# 3.net
KiCad netlist of a schematic drawn in Altium Designer
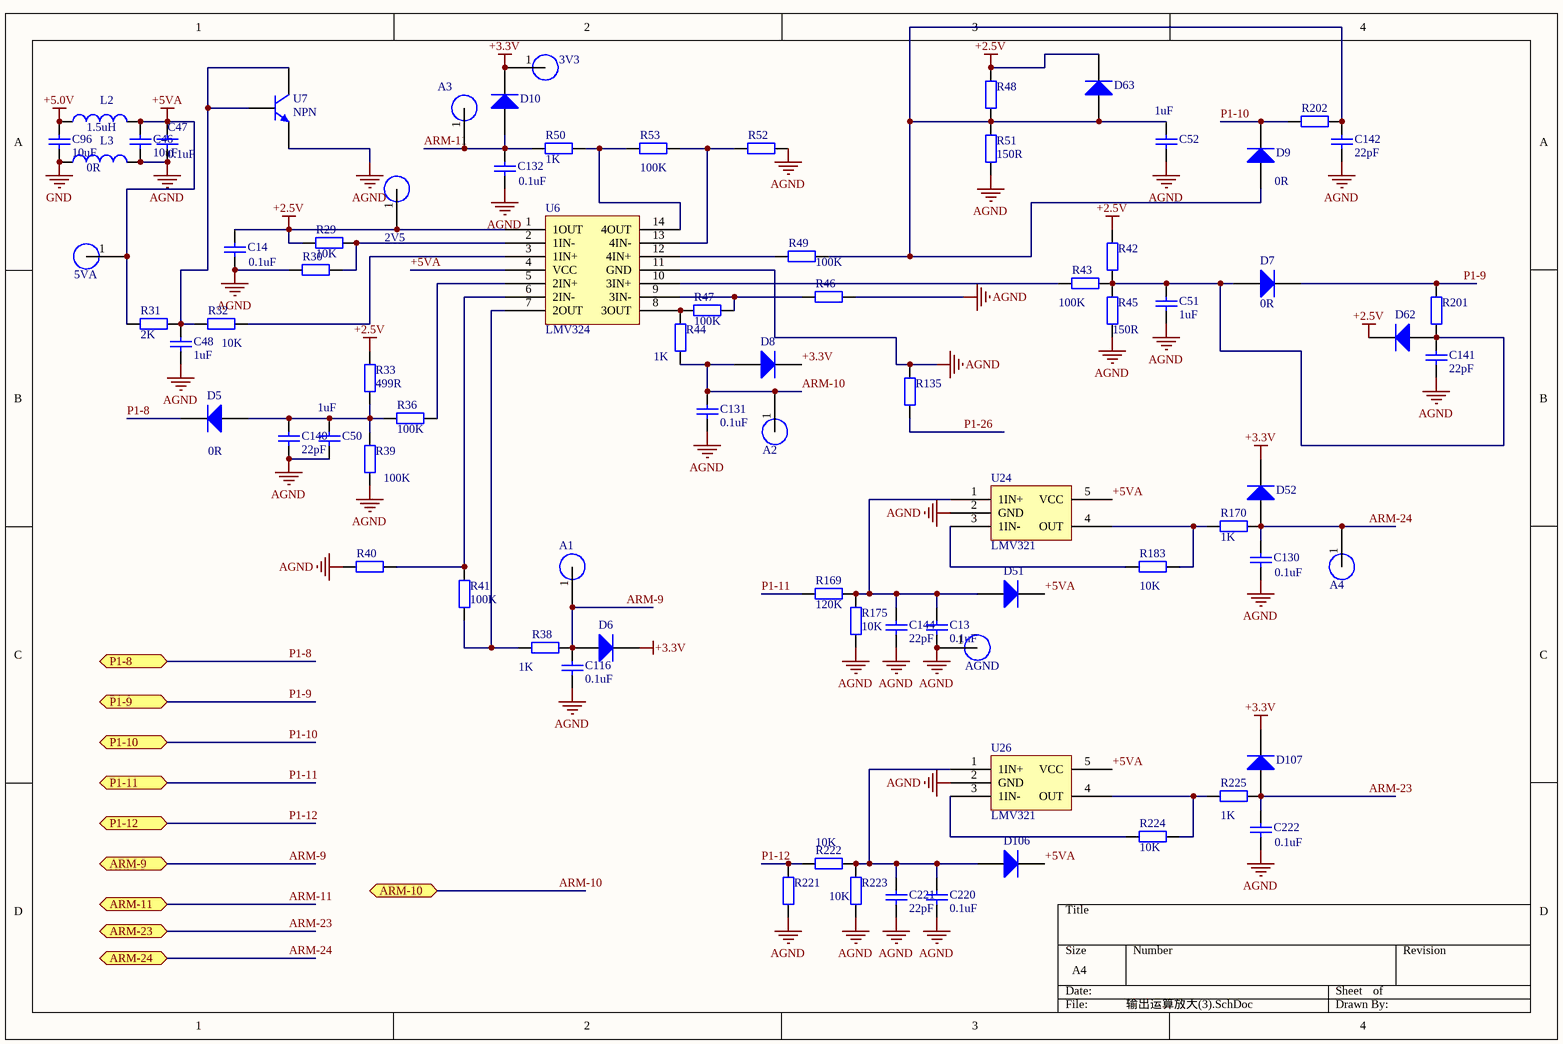
[diagram p0: 输出运算放大(3).SchDoc]

(export (version "E")
  (design (tool "Eeschema 10.0.6"))
  (components
    (comp (ref "2V5") (value "PIN") (footprint "圆形焊盘") (libsource (lib "圆孔") (part "Component_1")))
    (comp (ref "3V3") (value "PIN") (footprint "圆形焊盘") (libsource (lib "") (part "Component_1_1")))
    (comp (ref "5VA") (value "PIN") (footprint "圆形焊盘") (libsource (lib "") (part "Component_1_1")))
    (comp (ref "A1") (value "PIN") (footprint "圆形焊盘") (libsource (lib "圆孔") (part "Component_1")))
    (comp (ref "A2") (value "PIN") (footprint "圆形焊盘") (libsource (lib "圆孔") (part "Component_1")))
    (comp (ref "A3") (value "PIN") (footprint "圆形焊盘") (libsource (lib "圆孔") (part "Component_1")))
    (comp (ref "A4") (value "PIN") (footprint "圆形焊盘") (libsource (lib "圆孔") (part "Component_1")))
    (comp (ref "AGND") (value "PIN") (footprint "圆形焊盘") (libsource (lib "") (part "Component_1_1")))
    (comp (ref "C13")
      (value "0.1uF")
      (footprint "采集板3.0增加1路模拟量2:C0805")
      (description "Capacitor")
      (fields (field (name "Comment") "Cap") (field (name "PUBLISHER") "Altium Limited"))
      (libsource (lib "Miscellaneous Devices") (part "Cap"))
    )
    (comp (ref "C14")
      (value "0.1uF")
      (footprint "采集板3.0增加1路模拟量2:C0805")
      (description "Capacitor")
      (fields (field (name "Comment") "Cap") (field (name "PUBLISHER") "Altium Limited"))
      (libsource (lib "Miscellaneous Devices") (part "Cap"))
    )
    (comp (ref "C46")
      (value "10uF")
      (footprint "C1206")
      (description "Capacitor")
      (fields (field (name "Comment") "Cap") (field (name "PUBLISHER") "Altium Limited"))
      (libsource (lib "Miscellaneous Devices") (part "Cap"))
    )
    (comp (ref "C47")
      (value "0.1uF")
      (footprint "采集板3.0增加1路模拟量2:C0805")
      (description "Capacitor")
      (fields (field (name "Comment") "Cap") (field (name "PUBLISHER") "Altium Limited"))
      (libsource (lib "Miscellaneous Devices") (part "Cap"))
    )
    (comp (ref "C48")
      (value "1uF")
      (footprint "C0805")
      (description "Capacitor")
      (fields (field (name "Comment") "Cap") (field (name "PUBLISHER") "Altium Limited"))
      (libsource (lib "Miscellaneous Devices") (part "Cap"))
    )
    (comp (ref "C50")
      (value "1uF")
      (footprint "C0805")
      (description "Capacitor")
      (fields (field (name "Comment") "Cap") (field (name "PUBLISHER") "Altium Limited"))
      (libsource (lib "Miscellaneous Devices") (part "Cap"))
    )
    (comp (ref "C51")
      (value "1uF")
      (footprint "C0805")
      (description "Capacitor")
      (fields (field (name "Comment") "Cap") (field (name "PUBLISHER") "Altium Limited"))
      (libsource (lib "Miscellaneous Devices") (part "Cap"))
    )
    (comp (ref "C52")
      (value "1uF")
      (footprint "C0805")
      (description "Capacitor")
      (fields (field (name "Comment") "Cap") (field (name "PUBLISHER") "Altium Limited"))
      (libsource (lib "Miscellaneous Devices") (part "Cap"))
    )
    (comp (ref "C96")
      (value "10uF")
      (footprint "C1206")
      (description "Capacitor")
      (fields (field (name "Comment") "Cap") (field (name "PUBLISHER") "Altium Limited"))
      (libsource (lib "Miscellaneous Devices") (part "Cap"))
    )
    (comp (ref "C116")
      (value "0.1uF")
      (footprint "采集板3.0增加1路模拟量2:C0805")
      (description "Capacitor")
      (fields (field (name "Comment") "Cap") (field (name "PUBLISHER") "Altium Limited"))
      (libsource (lib "Miscellaneous Devices") (part "Cap"))
    )
    (comp (ref "C130")
      (value "0.1uF")
      (footprint "采集板3.0增加1路模拟量2:C0805")
      (description "Capacitor")
      (fields (field (name "Comment") "Cap") (field (name "PUBLISHER") "Altium Limited"))
      (libsource (lib "Miscellaneous Devices") (part "Cap"))
    )
    (comp (ref "C131")
      (value "0.1uF")
      (footprint "采集板3.0增加1路模拟量2:C0805")
      (description "Capacitor")
      (fields (field (name "Comment") "Cap") (field (name "PUBLISHER") "Altium Limited"))
      (libsource (lib "Miscellaneous Devices") (part "Cap"))
    )
    (comp (ref "C132")
      (value "0.1uF")
      (footprint "采集板3.0增加1路模拟量2:C0805")
      (description "Capacitor")
      (fields (field (name "Comment") "Cap") (field (name "PUBLISHER") "Altium Limited"))
      (libsource (lib "Miscellaneous Devices") (part "Cap"))
    )
    (comp (ref "C140")
      (value "22pF")
      (footprint "采集板3.0增加1路模拟量2:C0805")
      (description "Capacitor")
      (fields (field (name "Comment") "Cap") (field (name "PUBLISHER") "Altium Limited"))
      (libsource (lib "Miscellaneous Devices") (part "Cap"))
    )
    (comp (ref "C141")
      (value "22pF")
      (footprint "采集板3.0增加1路模拟量2:C0805")
      (description "Capacitor")
      (fields (field (name "Comment") "Cap") (field (name "PUBLISHER") "Altium Limited"))
      (libsource (lib "Miscellaneous Devices") (part "Cap"))
    )
    (comp (ref "C142")
      (value "22pF")
      (footprint "采集板3.0增加1路模拟量2:C0805")
      (description "Capacitor")
      (fields (field (name "Comment") "Cap") (field (name "PUBLISHER") "Altium Limited"))
      (libsource (lib "Miscellaneous Devices") (part "Cap"))
    )
    (comp (ref "C144")
      (value "22pF")
      (footprint "采集板3.0增加1路模拟量2:C0805")
      (description "Capacitor")
      (fields (field (name "Comment") "Cap") (field (name "PUBLISHER") "Altium Limited"))
      (libsource (lib "Miscellaneous Devices") (part "Cap"))
    )
    (comp (ref "C220")
      (value "0.1uF")
      (footprint "采集板3.0增加1路模拟量2:C0805")
      (description "Capacitor")
      (fields (field (name "Comment") "Cap") (field (name "PUBLISHER") "Altium Limited"))
      (libsource (lib "Miscellaneous Devices") (part "Cap"))
    )
    (comp (ref "C221")
      (value "22pF")
      (footprint "采集板3.0增加1路模拟量2:C0805")
      (description "Capacitor")
      (fields (field (name "Comment") "Cap") (field (name "PUBLISHER") "Altium Limited"))
      (libsource (lib "Miscellaneous Devices") (part "Cap"))
    )
    (comp (ref "C222")
      (value "0.1uF")
      (footprint "采集板3.0增加1路模拟量2:C0805")
      (description "Capacitor")
      (fields (field (name "Comment") "Cap") (field (name "PUBLISHER") "Altium Limited"))
      (libsource (lib "") (part "Cap_1"))
    )
    (comp (ref "D5")
      (value "0R")
      (footprint "SOD123")
      (description "1 Amp General Purpose Rectifier")
      (fields (field (name "Comment") "Diode 1N4007") (field (name "PUBLISHER") "Altium Limited"))
      (libsource (lib "Miscellaneous Devices") (part "Diode 1N4007"))
    )
    (comp (ref "D6")
      (value "Diode 1N4007")
      (footprint "SOD123")
      (description "1 Amp General Purpose Rectifier")
      (fields (field (name "PUBLISHER") "Altium Limited"))
      (libsource (lib "Miscellaneous Devices") (part "Diode 1N4007"))
    )
    (comp (ref "D7")
      (value "0R")
      (footprint "SOD123")
      (description "1 Amp General Purpose Rectifier")
      (fields (field (name "Comment") "Diode 1N4007") (field (name "PUBLISHER") "Altium Limited"))
      (libsource (lib "Miscellaneous Devices") (part "Diode 1N4007"))
    )
    (comp (ref "D8")
      (value "Diode 1N4007")
      (footprint "SOD123")
      (description "1 Amp General Purpose Rectifier")
      (fields (field (name "PUBLISHER") "Altium Limited"))
      (libsource (lib "Miscellaneous Devices") (part "Diode 1N4007"))
    )
    (comp (ref "D9")
      (value "0R")
      (footprint "SOD123")
      (description "1 Amp General Purpose Rectifier")
      (fields (field (name "Comment") "Diode 1N4007") (field (name "PUBLISHER") "Altium Limited"))
      (libsource (lib "Miscellaneous Devices") (part "Diode 1N4007"))
    )
    (comp (ref "D10")
      (value "Diode 1N4007")
      (footprint "SOD123")
      (description "1 Amp General Purpose Rectifier")
      (fields (field (name "PUBLISHER") "Altium Limited"))
      (libsource (lib "Miscellaneous Devices") (part "Diode 1N4007"))
    )
    (comp (ref "D51")
      (value "Diode 1N4007")
      (footprint "SOD123")
      (description "1 Amp General Purpose Rectifier")
      (fields (field (name "PUBLISHER") "Altium Limited"))
      (libsource (lib "Miscellaneous Devices") (part "Diode 1N4007"))
    )
    (comp (ref "D52")
      (value "Diode 1N4007")
      (footprint "SOD123")
      (description "1 Amp General Purpose Rectifier")
      (fields (field (name "PUBLISHER") "Altium Limited"))
      (libsource (lib "Miscellaneous Devices") (part "Diode 1N4007"))
    )
    (comp (ref "D62")
      (value "Diode 1N4007")
      (footprint "SOD123")
      (description "1 Amp General Purpose Rectifier")
      (fields (field (name "PUBLISHER") "Altium Limited"))
      (libsource (lib "Miscellaneous Devices") (part "Diode 1N4007"))
    )
    (comp (ref "D63")
      (value "Diode 1N4007")
      (footprint "SOD123")
      (description "1 Amp General Purpose Rectifier")
      (fields (field (name "PUBLISHER") "Altium Limited"))
      (libsource (lib "Miscellaneous Devices") (part "Diode 1N4007"))
    )
    (comp (ref "D106")
      (value "Diode 1N4007")
      (footprint "SOD123")
      (description "1 Amp General Purpose Rectifier")
      (fields (field (name "PUBLISHER") "Altium Limited"))
      (libsource (lib "Miscellaneous Devices") (part "Diode 1N4007"))
    )
    (comp (ref "D107")
      (value "Diode 1N4007")
      (footprint "SOD123")
      (description "1 Amp General Purpose Rectifier")
      (fields (field (name "PUBLISHER") "Altium Limited"))
      (libsource (lib "Miscellaneous Devices") (part "Diode 1N4007"))
    )
    (comp (ref "L2")
      (value "1.5uH")
      (footprint "C1206")
      (description "Inductor")
      (fields (field (name "PUBLISHER") "Altium Limited"))
      (libsource (lib "Miscellaneous Devices") (part "Inductor"))
    )
    (comp (ref "L3")
      (value "0R")
      (footprint "R1206")
      (description "Inductor")
      (fields (field (name "PUBLISHER") "Altium Limited"))
      (libsource (lib "Miscellaneous Devices") (part "Inductor"))
    )
    (comp (ref "R29")
      (value "10K")
      (footprint "采集板3.0增加1路模拟量2:R0805")
      (description "Resistor")
      (fields (field (name "Comment") "Res2") (field (name "PUBLISHER") "Altium Limited"))
      (libsource (lib "Miscellaneous Devices") (part "Res2"))
    )
    (comp (ref "R30")
      (value "Res2")
      (footprint "R0805")
      (description "Resistor")
      (fields (field (name "PUBLISHER") "Altium Limited"))
      (libsource (lib "") (part "Res2_3"))
    )
    (comp (ref "R31")
      (value "2K")
      (footprint "采集板3.0增加1路模拟量2:R0805")
      (description "Resistor")
      (fields (field (name "Comment") "Res2") (field (name "PUBLISHER") "Altium Limited"))
      (libsource (lib "") (part "Res2_3"))
    )
    (comp (ref "R32")
      (value "10K")
      (footprint "采集板3.0增加1路模拟量2:R0805")
      (description "Resistor")
      (fields (field (name "Comment") "Res2") (field (name "PUBLISHER") "Altium Limited"))
      (libsource (lib "Miscellaneous Devices") (part "Res2"))
    )
    (comp (ref "R33")
      (value "499R")
      (footprint "采集板3.0增加1路模拟量2:R0805")
      (description "Resistor")
      (fields (field (name "Comment") "Res2") (field (name "PUBLISHER") "Altium Limited"))
      (libsource (lib "") (part "Res2_1"))
    )
    (comp (ref "R36")
      (value "100K")
      (footprint "采集板3.0增加1路模拟量2:R0805")
      (description "Resistor")
      (fields (field (name "Comment") "Res2") (field (name "PUBLISHER") "Altium Limited"))
      (libsource (lib "") (part "Res2_3"))
    )
    (comp (ref "R38")
      (value "1K")
      (footprint "采集板3.0增加1路模拟量2:R0805")
      (description "Resistor")
      (fields (field (name "Comment") "Res2") (field (name "PUBLISHER") "Altium Limited"))
      (libsource (lib "") (part "Res2_3"))
    )
    (comp (ref "R39")
      (value "100K")
      (footprint "采集板3.0增加1路模拟量2:R0805")
      (description "Resistor")
      (fields (field (name "Comment") "Res2") (field (name "PUBLISHER") "Altium Limited"))
      (libsource (lib "") (part "Res2_2"))
    )
    (comp (ref "R40")
      (value "Res2")
      (footprint "R0805")
      (description "Resistor")
      (fields (field (name "PUBLISHER") "Altium Limited"))
      (libsource (lib "") (part "Res2_3"))
    )
    (comp (ref "R41")
      (value "100K")
      (footprint "采集板3.0增加1路模拟量2:R0805")
      (description "Resistor")
      (fields (field (name "Comment") "Res2") (field (name "PUBLISHER") "Altium Limited"))
      (libsource (lib "") (part "Res2_1"))
    )
    (comp (ref "R42")
      (value "Res2")
      (footprint "R0805")
      (description "Resistor")
      (fields (field (name "PUBLISHER") "Altium Limited"))
      (libsource (lib "") (part "Res2_1"))
    )
    (comp (ref "R43")
      (value "100K")
      (footprint "采集板3.0增加1路模拟量2:R0805")
      (description "Resistor")
      (fields (field (name "Comment") "Res2") (field (name "PUBLISHER") "Altium Limited"))
      (libsource (lib "Miscellaneous Devices") (part "Res2"))
    )
    (comp (ref "R44")
      (value "1K")
      (footprint "采集板3.0增加1路模拟量2:R0805")
      (description "Resistor")
      (fields (field (name "Comment") "Res2") (field (name "PUBLISHER") "Altium Limited"))
      (libsource (lib "") (part "Res2_2"))
    )
    (comp (ref "R45")
      (value "150R")
      (footprint "R0805")
      (description "Resistor")
      (fields (field (name "Comment") "150") (field (name "PUBLISHER") "Altium Limited"))
      (libsource (lib "") (part "Res2_2"))
    )
    (comp (ref "R46")
      (value "Res2")
      (footprint "R0805")
      (description "Resistor")
      (fields (field (name "PUBLISHER") "Altium Limited"))
      (libsource (lib "Miscellaneous Devices") (part "Res2"))
    )
    (comp (ref "R47")
      (value "100K")
      (footprint "采集板3.0增加1路模拟量2:R0805")
      (description "Resistor")
      (fields (field (name "Comment") "Res2") (field (name "PUBLISHER") "Altium Limited"))
      (libsource (lib "") (part "Res2_3"))
    )
    (comp (ref "R48")
      (value "Res2")
      (footprint "R0805")
      (description "Resistor")
      (fields (field (name "PUBLISHER") "Altium Limited"))
      (libsource (lib "") (part "Res2_1"))
    )
    (comp (ref "R49")
      (value "100K")
      (footprint "采集板3.0增加1路模拟量2:R0805")
      (description "Resistor")
      (fields (field (name "Comment") "Res2") (field (name "PUBLISHER") "Altium Limited"))
      (libsource (lib "Miscellaneous Devices") (part "Res2"))
    )
    (comp (ref "R50")
      (value "1K")
      (footprint "采集板3.0增加1路模拟量2:R0805")
      (description "Resistor")
      (fields (field (name "Comment") "Res2") (field (name "PUBLISHER") "Altium Limited"))
      (libsource (lib "") (part "Res2_3"))
    )
    (comp (ref "R51")
      (value "150R")
      (footprint "R0805")
      (description "Resistor")
      (fields (field (name "Comment") "Res2") (field (name "PUBLISHER") "Altium Limited"))
      (libsource (lib "") (part "Res2_2"))
    )
    (comp (ref "R52")
      (value "Res2")
      (footprint "R0805")
      (description "Resistor")
      (fields (field (name "PUBLISHER") "Altium Limited"))
      (libsource (lib "") (part "Res2_3"))
    )
    (comp (ref "R53")
      (value "100K")
      (footprint "采集板3.0增加1路模拟量2:R0805")
      (description "Resistor")
      (fields (field (name "Comment") "Res2") (field (name "PUBLISHER") "Altium Limited"))
      (libsource (lib "Miscellaneous Devices") (part "Res2"))
    )
    (comp (ref "R135")
      (value "Res2")
      (footprint "采集板3.0增加1路模拟量2:R0805")
      (description "Resistor")
      (fields (field (name "PUBLISHER") "Altium Limited"))
      (libsource (lib "") (part "Res2_2"))
    )
    (comp (ref "R169")
      (value "120K")
      (footprint "采集板3.0增加1路模拟量2:R0805")
      (description "Resistor")
      (fields (field (name "Comment") "Res2") (field (name "PUBLISHER") "Altium Limited"))
      (libsource (lib "") (part "Res2_3"))
    )
    (comp (ref "R170")
      (value "1K")
      (footprint "采集板3.0增加1路模拟量2:R0805")
      (description "Resistor")
      (fields (field (name "Comment") "Res2") (field (name "PUBLISHER") "Altium Limited"))
      (libsource (lib "") (part "Res2_3"))
    )
    (comp (ref "R175")
      (value "10K")
      (footprint "采集板3.0增加1路模拟量2:R0805")
      (description "Resistor")
      (fields (field (name "Comment") "Res2") (field (name "PUBLISHER") "Altium Limited"))
      (libsource (lib "") (part "Res2_1"))
    )
    (comp (ref "R183")
      (value "10K")
      (footprint "采集板3.0增加1路模拟量2:R0805")
      (description "Resistor")
      (fields (field (name "Comment") "Res2") (field (name "PUBLISHER") "Altium Limited"))
      (libsource (lib "Miscellaneous Devices") (part "Res2"))
    )
    (comp (ref "R201")
      (value "Res2")
      (footprint "R0805")
      (description "Resistor")
      (fields (field (name "PUBLISHER") "Altium Limited"))
      (libsource (lib "") (part "Res2_1"))
    )
    (comp (ref "R202")
      (value "Res2")
      (footprint "R0805")
      (description "Resistor")
      (fields (field (name "PUBLISHER") "Altium Limited"))
      (libsource (lib "Miscellaneous Devices") (part "Res2"))
    )
    (comp (ref "R221")
      (value "Res2")
      (footprint "R0805")
      (description "Resistor")
      (fields (field (name "PUBLISHER") "Altium Limited"))
      (libsource (lib "") (part "Res2_2"))
    )
    (comp (ref "R222")
      (value "10K")
      (footprint "采集板3.0增加1路模拟量2:R0805")
      (description "Resistor")
      (fields (field (name "Comment") "Res2") (field (name "PUBLISHER") "Altium Limited"))
      (libsource (lib "Miscellaneous Devices") (part "Res2"))
    )
    (comp (ref "R223")
      (value "10K")
      (footprint "采集板3.0增加1路模拟量2:R0805")
      (description "Resistor")
      (fields (field (name "Comment") "Res2") (field (name "PUBLISHER") "Altium Limited"))
      (libsource (lib "") (part "Res2_2"))
    )
    (comp (ref "R224")
      (value "10K")
      (footprint "采集板3.0增加1路模拟量2:R0805")
      (description "Resistor")
      (fields (field (name "Comment") "Res2") (field (name "PUBLISHER") "Altium Limited"))
      (libsource (lib "") (part "Res2_3"))
    )
    (comp (ref "R225")
      (value "1K")
      (footprint "采集板3.0增加1路模拟量2:R0805")
      (description "Resistor")
      (fields (field (name "Comment") "Res2") (field (name "PUBLISHER") "Altium Limited"))
      (libsource (lib "") (part "Res2_4"))
    )
    (comp (ref "U6") (value "LMV324") (footprint "SOP-14") (libsource (lib "LMV324") (part "Component_1")))
    (comp (ref "U7")
      (value "NPN")
      (footprint "SOT23-3")
      (description "NPN Bipolar Transistor")
      (fields (field (name "PUBLISHER") "Altium Limited"))
      (libsource (lib "Miscellaneous Devices") (part "NPN"))
    )
    (comp (ref "U24") (value "LMV321") (footprint "SOT23-5") (libsource (lib "LMV321") (part "Component_1")))
    (comp (ref "U26") (value "LMV321") (footprint "SOT23-5") (libsource (lib "LMV321") (part "Component_1")))
  )
  (nets
    (net (code "1") (name "+2.5V") (class "Default")
      (node (ref "2V5") (pin "1") (pinfunction "1_1") (pintype "passive"))
      (node (ref "C14") (pin "2") (pinfunction "2_2") (pintype "passive"))
      (node (ref "D62") (pin "2") (pinfunction "K_2") (pintype "passive"))
      (node (ref "D63") (pin "2") (pinfunction "K_2") (pintype "passive"))
      (node (ref "R29") (pin "2") (pinfunction "2_2") (pintype "passive"))
      (node (ref "R33") (pin "2") (pinfunction "2_2") (pintype "passive"))
      (node (ref "R42") (pin "2") (pinfunction "2_2") (pintype "passive"))
      (node (ref "R48") (pin "2") (pinfunction "2_2") (pintype "passive"))
      (node (ref "U6") (pin "1") (pinfunction "1OUT_1") (pintype "passive"))
    )
    (net (code "2") (name "+3.3V") (class "Default")
      (node (ref "3V3") (pin "1") (pinfunction "1_1") (pintype "passive"))
      (node (ref "D10") (pin "2") (pinfunction "K_2") (pintype "passive"))
      (node (ref "D107") (pin "2") (pinfunction "K_2") (pintype "passive"))
      (node (ref "D52") (pin "2") (pinfunction "K_2") (pintype "passive"))
      (node (ref "D6") (pin "2") (pinfunction "K_2") (pintype "passive"))
      (node (ref "D8") (pin "2") (pinfunction "K_2") (pintype "passive"))
    )
    (net (code "3") (name "+5.0V") (class "Default")
      (node (ref "C96") (pin "1") (pinfunction "1_1") (pintype "passive"))
      (node (ref "L2") (pin "1") (pinfunction "1_1") (pintype "passive"))
    )
    (net (code "4") (name "+5VA") (class "Default")
      (node (ref "5VA") (pin "1") (pinfunction "1_1") (pintype "passive"))
      (node (ref "C46") (pin "1") (pinfunction "1_1") (pintype "passive"))
      (node (ref "C47") (pin "2") (pinfunction "2_2") (pintype "passive"))
      (node (ref "D106") (pin "2") (pinfunction "K_2") (pintype "passive"))
      (node (ref "D51") (pin "2") (pinfunction "K_2") (pintype "passive"))
      (node (ref "L2") (pin "2") (pinfunction "2_2") (pintype "passive"))
      (node (ref "R31") (pin "1") (pinfunction "1_1") (pintype "passive"))
      (node (ref "U24") (pin "5") (pinfunction "VCC_5") (pintype "passive"))
      (node (ref "U26") (pin "5") (pinfunction "VCC_5") (pintype "passive"))
      (node (ref "U6") (pin "4") (pinfunction "VCC_4") (pintype "passive"))
    )
    (net (code "5") (name "/ARM-9") (class "Default")
      (node (ref "A1") (pin "1") (pinfunction "1_1") (pintype "passive"))
      (node (ref "C116") (pin "1") (pinfunction "1_1") (pintype "passive"))
      (node (ref "D6") (pin "1") (pinfunction "A_1") (pintype "passive"))
      (node (ref "R38") (pin "2") (pinfunction "2_2") (pintype "passive"))
    )
    (net (code "6") (name "/ARM-10") (class "Default")
      (node (ref "A2") (pin "1") (pinfunction "1_1") (pintype "passive"))
      (node (ref "C131") (pin "1") (pinfunction "1_1") (pintype "passive"))
      (node (ref "D8") (pin "1") (pinfunction "A_1") (pintype "passive"))
      (node (ref "R44") (pin "2") (pinfunction "2_2") (pintype "passive"))
    )
    (net (code "7") (name "/ARM-11") (class "Default")
      (node (ref "A3") (pin "1") (pinfunction "1_1") (pintype "passive"))
      (node (ref "C132") (pin "2") (pinfunction "2_2") (pintype "passive"))
      (node (ref "D10") (pin "1") (pinfunction "A_1") (pintype "passive"))
      (node (ref "R50") (pin "1") (pinfunction "1_1") (pintype "passive"))
    )
    (net (code "8") (name "/ARM-23") (class "Default")
      (node (ref "C222") (pin "1") (pinfunction "2_1") (pintype "passive"))
      (node (ref "D107") (pin "1") (pinfunction "A_1") (pintype "passive"))
      (node (ref "R225") (pin "2") (pinfunction "1_2") (pintype "passive"))
    )
    (net (code "9") (name "/ARM-24") (class "Default")
      (node (ref "A4") (pin "1") (pinfunction "1_1") (pintype "passive"))
      (node (ref "C130") (pin "2") (pinfunction "2_2") (pintype "passive"))
      (node (ref "D52") (pin "1") (pinfunction "A_1") (pintype "passive"))
      (node (ref "R170") (pin "2") (pinfunction "2_2") (pintype "passive"))
    )
    (net (code "10") (name "/P1-8") (class "Default")
      (node (ref "D5") (pin "2") (pinfunction "K_2") (pintype "passive"))
    )
    (net (code "11") (name "/P1-9") (class "Default")
      (node (ref "D7") (pin "2") (pinfunction "K_2") (pintype "passive"))
      (node (ref "R201") (pin "2") (pinfunction "2_2") (pintype "passive"))
    )
    (net (code "12") (name "/P1-10") (class "Default")
      (node (ref "D9") (pin "2") (pinfunction "K_2") (pintype "passive"))
      (node (ref "R202") (pin "2") (pinfunction "2_2") (pintype "passive"))
    )
    (net (code "13") (name "/P1-11") (class "Default")
      (node (ref "R169") (pin "1") (pinfunction "1_1") (pintype "passive"))
    )
    (net (code "14") (name "/P1-12") (class "Default")
      (node (ref "R221") (pin "1") (pinfunction "1_1") (pintype "passive"))
      (node (ref "R222") (pin "2") (pinfunction "2_2") (pintype "passive"))
    )
    (net (code "15") (name "/P1-26") (class "Default")
      (node (ref "R135") (pin "2") (pinfunction "2_2") (pintype "passive"))
    )
    (net (code "16") (name "AGND") (class "Default")
      (node (ref "AGND") (pin "1") (pinfunction "1_1") (pintype "passive"))
      (node (ref "C116") (pin "2") (pinfunction "2_2") (pintype "passive"))
      (node (ref "C13") (pin "2") (pinfunction "2_2") (pintype "passive"))
      (node (ref "C130") (pin "1") (pinfunction "1_1") (pintype "passive"))
      (node (ref "C131") (pin "2") (pinfunction "2_2") (pintype "passive"))
      (node (ref "C132") (pin "1") (pinfunction "1_1") (pintype "passive"))
      (node (ref "C14") (pin "1") (pinfunction "1_1") (pintype "passive"))
      (node (ref "C140") (pin "2") (pinfunction "2_2") (pintype "passive"))
      (node (ref "C141") (pin "2") (pinfunction "2_2") (pintype "passive"))
      (node (ref "C142") (pin "2") (pinfunction "2_2") (pintype "passive"))
      (node (ref "C144") (pin "2") (pinfunction "2_2") (pintype "passive"))
      (node (ref "C220") (pin "2") (pinfunction "2_2") (pintype "passive"))
      (node (ref "C221") (pin "2") (pinfunction "2_2") (pintype "passive"))
      (node (ref "C222") (pin "2") (pinfunction "1_2") (pintype "passive"))
      (node (ref "C46") (pin "2") (pinfunction "2_2") (pintype "passive"))
      (node (ref "C47") (pin "1") (pinfunction "1_1") (pintype "passive"))
      (node (ref "C48") (pin "2") (pinfunction "2_2") (pintype "passive"))
      (node (ref "C50") (pin "1") (pinfunction "1_1") (pintype "passive"))
      (node (ref "C51") (pin "1") (pinfunction "1_1") (pintype "passive"))
      (node (ref "C52") (pin "1") (pinfunction "1_1") (pintype "passive"))
      (node (ref "L3") (pin "2") (pinfunction "2_2") (pintype "passive"))
      (node (ref "R135") (pin "1") (pinfunction "1_1") (pintype "passive"))
      (node (ref "R175") (pin "1") (pinfunction "1_1") (pintype "passive"))
      (node (ref "R221") (pin "2") (pinfunction "2_2") (pintype "passive"))
      (node (ref "R223") (pin "2") (pinfunction "2_2") (pintype "passive"))
      (node (ref "R30") (pin "1") (pinfunction "1_1") (pintype "passive"))
      (node (ref "R39") (pin "2") (pinfunction "2_2") (pintype "passive"))
      (node (ref "R40") (pin "1") (pinfunction "1_1") (pintype "passive"))
      (node (ref "R45") (pin "2") (pinfunction "2_2") (pintype "passive"))
      (node (ref "R46") (pin "1") (pinfunction "1_1") (pintype "passive"))
      (node (ref "R51") (pin "2") (pinfunction "2_2") (pintype "passive"))
      (node (ref "R52") (pin "2") (pinfunction "2_2") (pintype "passive"))
      (node (ref "U24") (pin "2") (pinfunction "GND_2") (pintype "passive"))
      (node (ref "U26") (pin "2") (pinfunction "GND_2") (pintype "passive"))
      (node (ref "U6") (pin "11") (pinfunction "GND_11") (pintype "passive"))
      (node (ref "U7") (pin "3") (pinfunction "E_3") (pintype "passive"))
    )
    (net (code "17") (name "GND") (class "Default")
      (node (ref "C96") (pin "2") (pinfunction "2_2") (pintype "passive"))
      (node (ref "L3") (pin "1") (pinfunction "1_1") (pintype "passive"))
    )
    (net (code "18") (name "Net-(D5-A)") (class "Default")
      (node (ref "C140") (pin "1") (pinfunction "1_1") (pintype "passive"))
      (node (ref "C50") (pin "2") (pinfunction "2_2") (pintype "passive"))
      (node (ref "D5") (pin "1") (pinfunction "A_1") (pintype "passive"))
      (node (ref "R33") (pin "1") (pinfunction "1_1") (pintype "passive"))
      (node (ref "R36") (pin "1") (pinfunction "1_1") (pintype "passive"))
      (node (ref "R39") (pin "1") (pinfunction "1_1") (pintype "passive"))
    )
    (net (code "19") (name "Net-(D51-A)") (class "Default")
      (node (ref "C13") (pin "1") (pinfunction "1_1") (pintype "passive"))
      (node (ref "C144") (pin "1") (pinfunction "1_1") (pintype "passive"))
      (node (ref "D51") (pin "1") (pinfunction "A_1") (pintype "passive"))
      (node (ref "R169") (pin "2") (pinfunction "2_2") (pintype "passive"))
      (node (ref "R175") (pin "2") (pinfunction "2_2") (pintype "passive"))
      (node (ref "U24") (pin "1") (pinfunction "1IN+_1") (pintype "passive"))
    )
    (net (code "20") (name "Net-(D62-A)") (class "Default")
      (node (ref "C141") (pin "1") (pinfunction "1_1") (pintype "passive"))
      (node (ref "C51") (pin "2") (pinfunction "2_2") (pintype "passive"))
      (node (ref "D62") (pin "1") (pinfunction "A_1") (pintype "passive"))
      (node (ref "D7") (pin "1") (pinfunction "A_1") (pintype "passive"))
      (node (ref "R201") (pin "1") (pinfunction "1_1") (pintype "passive"))
      (node (ref "R42") (pin "1") (pinfunction "1_1") (pintype "passive"))
      (node (ref "R43") (pin "1") (pinfunction "1_1") (pintype "passive"))
      (node (ref "R45") (pin "1") (pinfunction "1_1") (pintype "passive"))
    )
    (net (code "21") (name "Net-(D63-A)") (class "Default")
      (node (ref "C142") (pin "1") (pinfunction "1_1") (pintype "passive"))
      (node (ref "C52") (pin "2") (pinfunction "2_2") (pintype "passive"))
      (node (ref "D63") (pin "1") (pinfunction "A_1") (pintype "passive"))
      (node (ref "D9") (pin "1") (pinfunction "A_1") (pintype "passive"))
      (node (ref "R202") (pin "1") (pinfunction "1_1") (pintype "passive"))
      (node (ref "R48") (pin "1") (pinfunction "1_1") (pintype "passive"))
      (node (ref "R49") (pin "1") (pinfunction "1_1") (pintype "passive"))
      (node (ref "R51") (pin "1") (pinfunction "1_1") (pintype "passive"))
    )
    (net (code "22") (name "Net-(D106-A)") (class "Default")
      (node (ref "C220") (pin "1") (pinfunction "1_1") (pintype "passive"))
      (node (ref "C221") (pin "1") (pinfunction "1_1") (pintype "passive"))
      (node (ref "D106") (pin "1") (pinfunction "A_1") (pintype "passive"))
      (node (ref "R222") (pin "1") (pinfunction "1_1") (pintype "passive"))
      (node (ref "R223") (pin "1") (pinfunction "1_1") (pintype "passive"))
      (node (ref "U26") (pin "1") (pinfunction "1IN+_1") (pintype "passive"))
    )
    (net (code "23") (name "Net-(R225-2)") (class "Default")
      (node (ref "R224") (pin "2") (pinfunction "2_2") (pintype "passive"))
      (node (ref "R225") (pin "1") (pinfunction "2_1") (pintype "passive"))
      (node (ref "U26") (pin "4") (pinfunction "OUT_4") (pintype "passive"))
    )
    (net (code "24") (name "Net-(U6-1IN+)") (class "Default")
      (node (ref "R32") (pin "1") (pinfunction "1_1") (pintype "passive"))
      (node (ref "U6") (pin "3") (pinfunction "1IN+_3") (pintype "passive"))
    )
    (net (code "25") (name "Net-(U6-1IN-)") (class "Default")
      (node (ref "R29") (pin "1") (pinfunction "1_1") (pintype "passive"))
      (node (ref "R30") (pin "2") (pinfunction "2_2") (pintype "passive"))
      (node (ref "U6") (pin "2") (pinfunction "1IN-_2") (pintype "passive"))
    )
    (net (code "26") (name "Net-(U6-2IN+)") (class "Default")
      (node (ref "R36") (pin "2") (pinfunction "2_2") (pintype "passive"))
      (node (ref "U6") (pin "5") (pinfunction "2IN+_5") (pintype "passive"))
    )
    (net (code "27") (name "Net-(U6-2IN-)") (class "Default")
      (node (ref "R40") (pin "2") (pinfunction "2_2") (pintype "passive"))
      (node (ref "R41") (pin "2") (pinfunction "2_2") (pintype "passive"))
      (node (ref "U6") (pin "6") (pinfunction "2IN-_6") (pintype "passive"))
    )
    (net (code "28") (name "Net-(U6-2OUT)") (class "Default")
      (node (ref "R38") (pin "1") (pinfunction "1_1") (pintype "passive"))
      (node (ref "R41") (pin "1") (pinfunction "1_1") (pintype "passive"))
      (node (ref "U6") (pin "7") (pinfunction "2OUT_7") (pintype "passive"))
    )
    (net (code "29") (name "Net-(U6-3IN+)") (class "Default")
      (node (ref "R43") (pin "2") (pinfunction "2_2") (pintype "passive"))
      (node (ref "U6") (pin "10") (pinfunction "3IN+_10") (pintype "passive"))
    )
    (net (code "30") (name "Net-(U6-3IN-)") (class "Default")
      (node (ref "R46") (pin "2") (pinfunction "2_2") (pintype "passive"))
      (node (ref "R47") (pin "2") (pinfunction "2_2") (pintype "passive"))
      (node (ref "U6") (pin "9") (pinfunction "3IN-_9") (pintype "passive"))
    )
    (net (code "31") (name "Net-(U6-3OUT)") (class "Default")
      (node (ref "R44") (pin "1") (pinfunction "1_1") (pintype "passive"))
      (node (ref "R47") (pin "1") (pinfunction "1_1") (pintype "passive"))
      (node (ref "U6") (pin "8") (pinfunction "3OUT_8") (pintype "passive"))
    )
    (net (code "32") (name "Net-(U6-4IN+)") (class "Default")
      (node (ref "R49") (pin "2") (pinfunction "2_2") (pintype "passive"))
      (node (ref "U6") (pin "12") (pinfunction "4IN+_12") (pintype "passive"))
    )
    (net (code "33") (name "Net-(U6-4IN-)") (class "Default")
      (node (ref "R52") (pin "1") (pinfunction "1_1") (pintype "passive"))
      (node (ref "R53") (pin "1") (pinfunction "1_1") (pintype "passive"))
      (node (ref "U6") (pin "13") (pinfunction "4IN-_13") (pintype "passive"))
    )
    (net (code "34") (name "Net-(U6-4OUT)") (class "Default")
      (node (ref "R50") (pin "2") (pinfunction "2_2") (pintype "passive"))
      (node (ref "R53") (pin "2") (pinfunction "2_2") (pintype "passive"))
      (node (ref "U6") (pin "14") (pinfunction "4OUT_14") (pintype "passive"))
    )
    (net (code "35") (name "Net-(U7-B)") (class "Default")
      (node (ref "C48") (pin "1") (pinfunction "1_1") (pintype "passive"))
      (node (ref "R31") (pin "2") (pinfunction "2_2") (pintype "passive"))
      (node (ref "R32") (pin "2") (pinfunction "2_2") (pintype "passive"))
      (node (ref "U7") (pin "1") (pinfunction "C_1") (pintype "passive"))
      (node (ref "U7") (pin "2") (pinfunction "B_2") (pintype "passive"))
    )
    (net (code "36") (name "Net-(U24-1IN-)") (class "Default")
      (node (ref "R183") (pin "2") (pinfunction "2_2") (pintype "passive"))
      (node (ref "U24") (pin "3") (pinfunction "1IN-_3") (pintype "passive"))
    )
    (net (code "37") (name "Net-(U24-OUT)") (class "Default")
      (node (ref "R170") (pin "1") (pinfunction "1_1") (pintype "passive"))
      (node (ref "R183") (pin "1") (pinfunction "1_1") (pintype "passive"))
      (node (ref "U24") (pin "4") (pinfunction "OUT_4") (pintype "passive"))
    )
    (net (code "38") (name "Net-(U26-1IN-)") (class "Default")
      (node (ref "R224") (pin "1") (pinfunction "1_1") (pintype "passive"))
      (node (ref "U26") (pin "3") (pinfunction "1IN-_3") (pintype "passive"))
    )
  )
)
